# SENSORS.net
KiCad netlist of a schematic drawn in Altium Designer
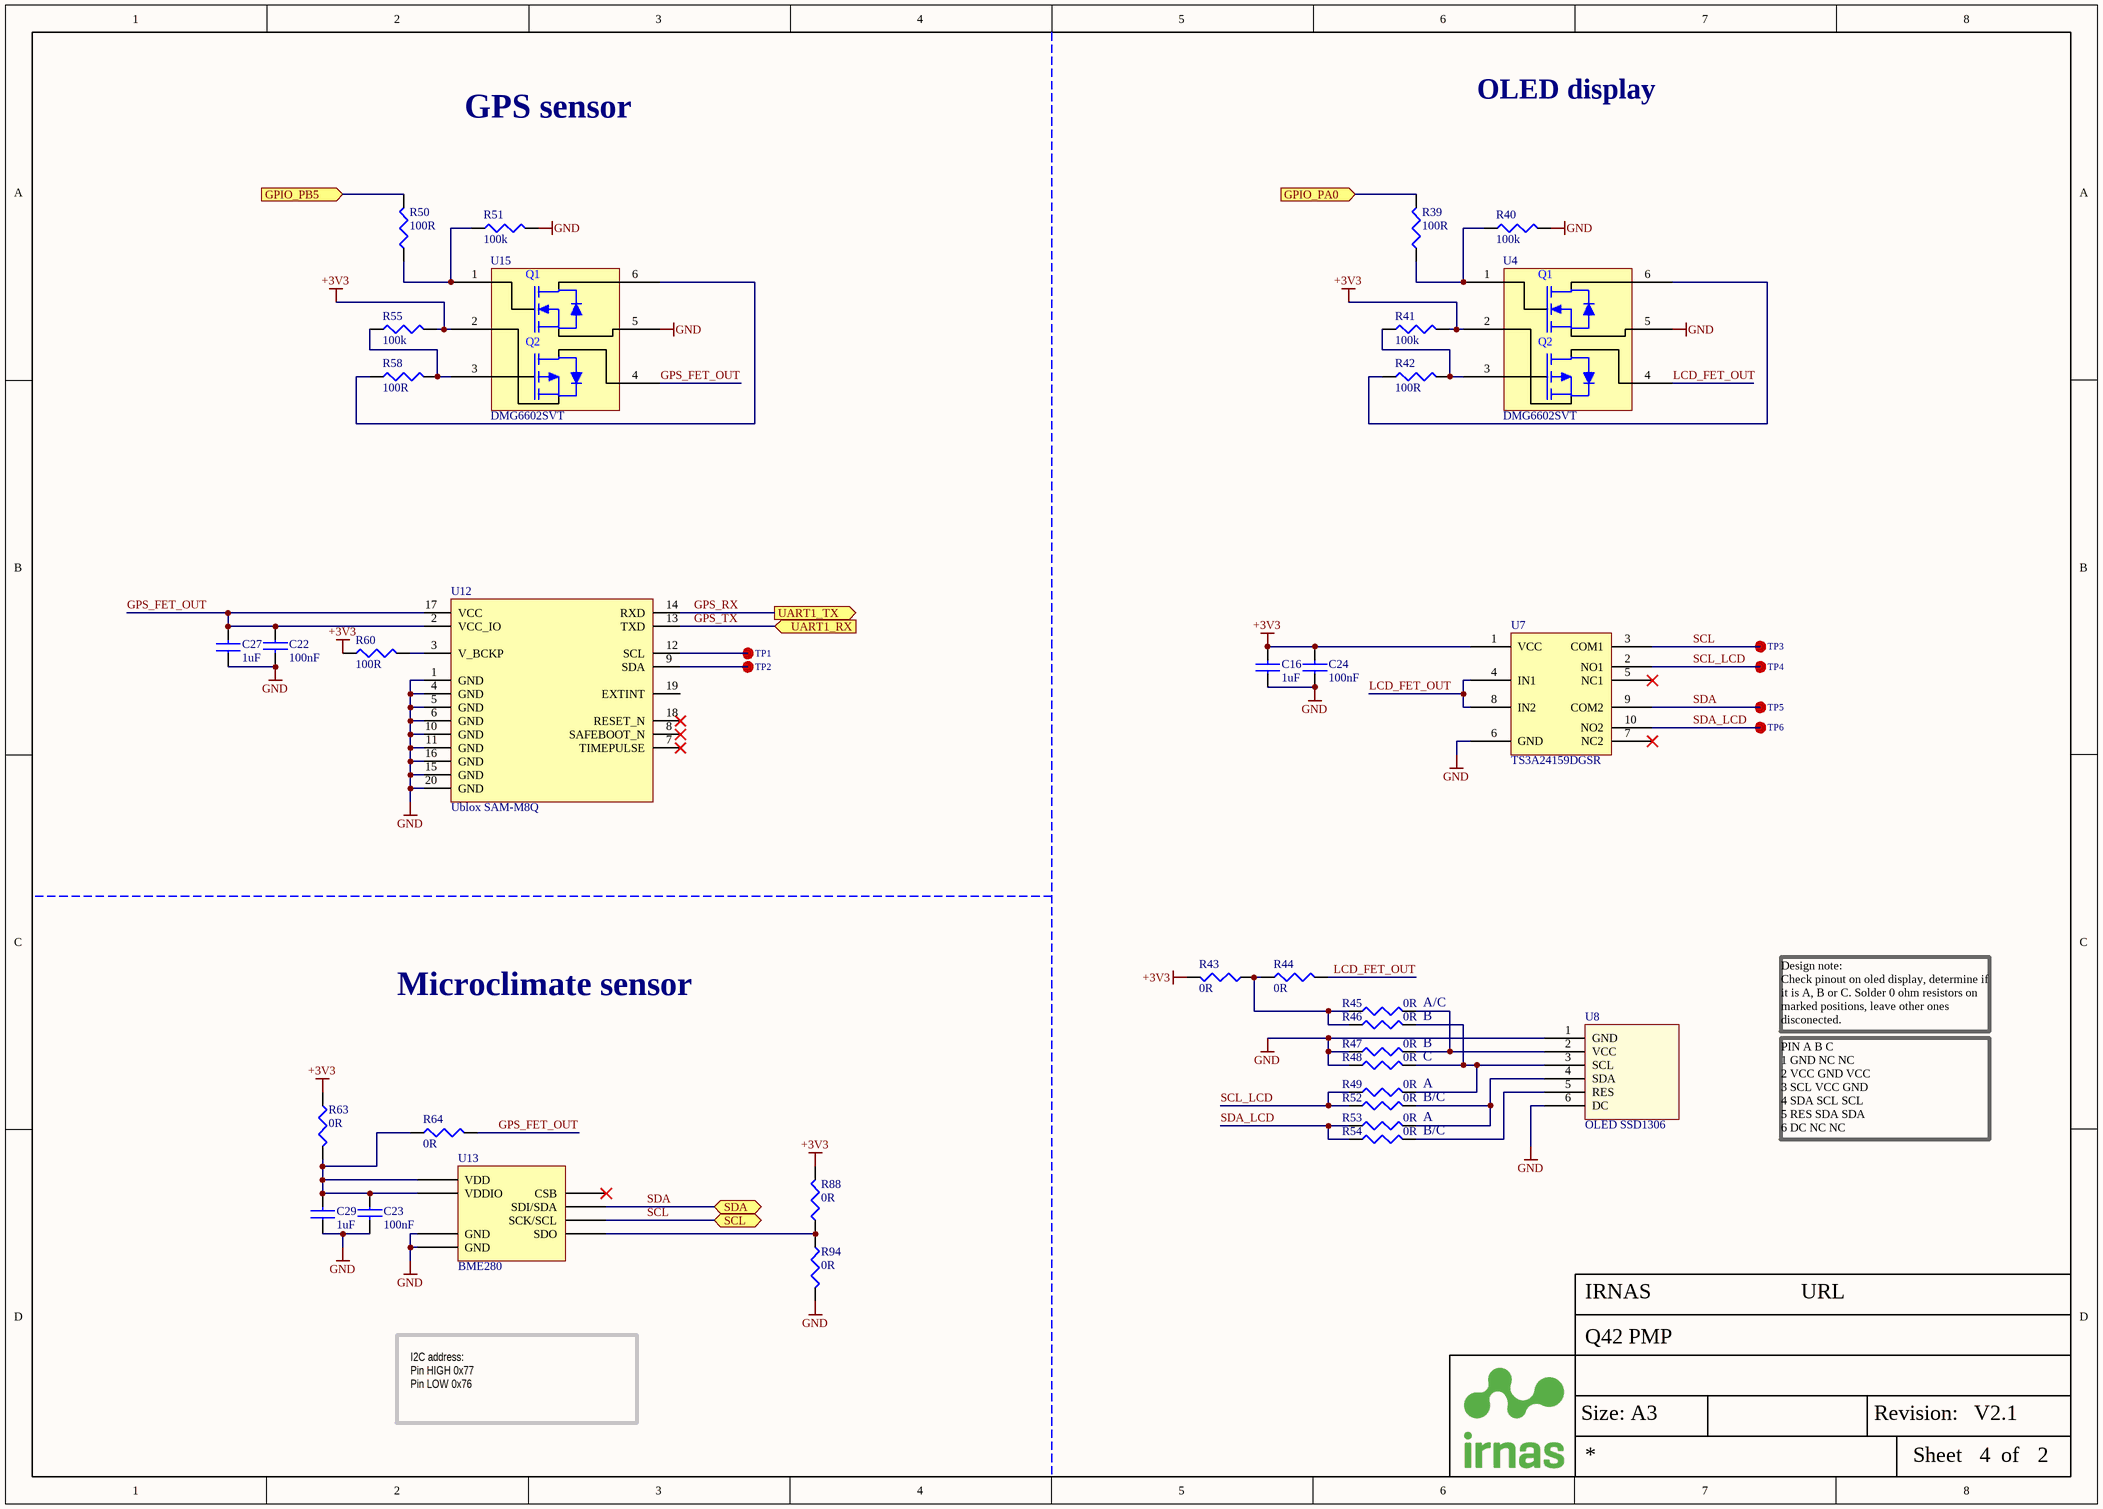
[diagram p0: SENSORS.SchDoc]

(export (version "E")
  (design (tool "Eeschema 10.0.6"))
  (components
    (comp (ref "C16")
      (value "1uF")
      (footprint "CAP0603")
      (description "MURATA - GRM188R61H105KAALD - CAP, MLCC, X5R, 1UF, 50V, 0603")
      (fields
        (field (name "MANUFACTURER") "MURATA")
        (field (name "MANUFACTURER PART NUMBER") "GRM188R61H105KAALD")
      )
      (libsource (lib "Passive") (part "C - 1uF"))
    )
    (comp (ref "C22")
      (value "100nF")
      (footprint "CAP0603")
      (description "MURATA - GRM188R71C104KA01J - CAP, MLCC, X7R, 0.1UF, 16V, 0603")
      (fields
        (field (name "MANUFACTURER") "MURATA")
        (field (name "MANUFACTURER PART NUMBER") "GRM188R71C104KA01J")
      )
      (libsource (lib "Passive") (part "C - 100nF"))
    )
    (comp (ref "C23")
      (value "100nF")
      (footprint "CAP0603")
      (description "MURATA - GRM188R71C104KA01J - CAP, MLCC, X7R, 0.1UF, 16V, 0603")
      (fields
        (field (name "MANUFACTURER") "MURATA")
        (field (name "MANUFACTURER PART NUMBER") "GRM188R71C104KA01J")
      )
      (libsource (lib "Passive") (part "C - 100nF"))
    )
    (comp (ref "C24")
      (value "100nF")
      (footprint "CAP0603")
      (description "MURATA - GRM188R71C104KA01J - CAP, MLCC, X7R, 0.1UF, 16V, 0603")
      (fields
        (field (name "MANUFACTURER") "MURATA")
        (field (name "MANUFACTURER PART NUMBER") "GRM188R71C104KA01J")
      )
      (libsource (lib "Passive") (part "C - 100nF"))
    )
    (comp (ref "C27")
      (value "1uF")
      (footprint "CAP0603")
      (description "MURATA - GRM188R61H105KAALD - CAP, MLCC, X5R, 1UF, 50V, 0603")
      (fields
        (field (name "MANUFACTURER") "MURATA")
        (field (name "MANUFACTURER PART NUMBER") "GRM188R61H105KAALD")
      )
      (libsource (lib "Passive") (part "C - 1uF"))
    )
    (comp (ref "C29")
      (value "1uF")
      (footprint "CAP0603")
      (description "MURATA - GRM188R61H105KAALD - CAP, MLCC, X5R, 1UF, 50V, 0603")
      (fields
        (field (name "MANUFACTURER") "MURATA")
        (field (name "MANUFACTURER PART NUMBER") "GRM188R61H105KAALD")
      )
      (libsource (lib "Passive") (part "C - 1uF"))
    )
    (comp (ref "R39")
      (value "100R")
      (footprint "RES0603")
      (description "MULTICOMP - MC0063W06031100R - RES, THICK FILM, 100R, 1%, 0.063W, 0603")
      (fields
        (field (name "MANUFACTURER") "MULTICOMP")
        (field (name "MANUFACTURER PART NUMBER") "MC0063W06031100R")
      )
      (libsource (lib "Passive") (part "R - 100R"))
    )
    (comp (ref "R40")
      (value "100k")
      (footprint "RES0603")
      (description "MULTICOMP - MCMR06X104 JTL - RES, CERAMIC, 100K, 5%, 0.1W, 0603")
      (fields
        (field (name "MANUFACTURER") "MULTICOMP")
        (field (name "MANUFACTURER PART NUMBER") "MCMR06X104 JTL")
      )
      (libsource (lib "Passive") (part "R - 100k"))
    )
    (comp (ref "R41")
      (value "100k")
      (footprint "RES0603")
      (description "MULTICOMP - MCMR06X104 JTL - RES, CERAMIC, 100K, 5%, 0.1W, 0603")
      (fields
        (field (name "MANUFACTURER") "MULTICOMP")
        (field (name "MANUFACTURER PART NUMBER") "MCMR06X104 JTL")
      )
      (libsource (lib "Passive") (part "R - 100k"))
    )
    (comp (ref "R42")
      (value "100R")
      (footprint "RES0603")
      (description "MULTICOMP - MC0063W06031100R - RES, THICK FILM, 100R, 1%, 0.063W, 0603")
      (fields
        (field (name "MANUFACTURER") "MULTICOMP")
        (field (name "MANUFACTURER PART NUMBER") "MC0063W06031100R")
      )
      (libsource (lib "Passive") (part "R - 100R"))
    )
    (comp (ref "R43")
      (value "0R")
      (footprint "RES0603")
      (description "BOURNS - CR0603-J/-000ELF - RES, THICK FILM, 0R, 5%, 0.1W, 0603")
      (fields
        (field (name "MANUFACTURER") "BOURNS")
        (field (name "MANUFACTURER PART NUMBER") "CR0603-J/-000ELF")
      )
      (libsource (lib "Passive") (part "R - 0R"))
    )
    (comp (ref "R44")
      (value "0R")
      (footprint "RES0603")
      (description "BOURNS - CR0603-J/-000ELF - RES, THICK FILM, 0R, 5%, 0.1W, 0603")
      (fields
        (field (name "MANUFACTURER") "BOURNS")
        (field (name "MANUFACTURER PART NUMBER") "CR0603-J/-000ELF")
      )
      (libsource (lib "Passive") (part "R - 0R"))
    )
    (comp (ref "R45")
      (value "0R")
      (footprint "RES0603")
      (description "BOURNS - CR0603-J/-000ELF - RES, THICK FILM, 0R, 5%, 0.1W, 0603")
      (fields
        (field (name "MANUFACTURER") "BOURNS")
        (field (name "MANUFACTURER PART NUMBER") "CR0603-J/-000ELF")
      )
      (libsource (lib "Passive") (part "R - 0R"))
    )
    (comp (ref "R46")
      (value "0R")
      (footprint "RES0603")
      (description "BOURNS - CR0603-J/-000ELF - RES, THICK FILM, 0R, 5%, 0.1W, 0603")
      (fields
        (field (name "MANUFACTURER") "BOURNS")
        (field (name "MANUFACTURER PART NUMBER") "CR0603-J/-000ELF")
      )
      (libsource (lib "Passive") (part "R - 0R"))
    )
    (comp (ref "R47")
      (value "0R")
      (footprint "RES0603")
      (description "BOURNS - CR0603-J/-000ELF - RES, THICK FILM, 0R, 5%, 0.1W, 0603")
      (fields
        (field (name "MANUFACTURER") "BOURNS")
        (field (name "MANUFACTURER PART NUMBER") "CR0603-J/-000ELF")
      )
      (libsource (lib "Passive") (part "R - 0R"))
    )
    (comp (ref "R48")
      (value "0R")
      (footprint "RES0603")
      (description "BOURNS - CR0603-J/-000ELF - RES, THICK FILM, 0R, 5%, 0.1W, 0603")
      (fields
        (field (name "MANUFACTURER") "BOURNS")
        (field (name "MANUFACTURER PART NUMBER") "CR0603-J/-000ELF")
      )
      (libsource (lib "Passive") (part "R - 0R"))
    )
    (comp (ref "R49")
      (value "0R")
      (footprint "RES0603")
      (description "BOURNS - CR0603-J/-000ELF - RES, THICK FILM, 0R, 5%, 0.1W, 0603")
      (fields
        (field (name "MANUFACTURER") "BOURNS")
        (field (name "MANUFACTURER PART NUMBER") "CR0603-J/-000ELF")
      )
      (libsource (lib "Passive") (part "R - 0R"))
    )
    (comp (ref "R50")
      (value "100R")
      (footprint "RES0603")
      (description "MULTICOMP - MC0063W06031100R - RES, THICK FILM, 100R, 1%, 0.063W, 0603")
      (fields
        (field (name "MANUFACTURER") "MULTICOMP")
        (field (name "MANUFACTURER PART NUMBER") "MC0063W06031100R")
      )
      (libsource (lib "Passive") (part "R - 100R"))
    )
    (comp (ref "R51")
      (value "100k")
      (footprint "RES0603")
      (description "MULTICOMP - MCMR06X104 JTL - RES, CERAMIC, 100K, 5%, 0.1W, 0603")
      (fields
        (field (name "MANUFACTURER") "MULTICOMP")
        (field (name "MANUFACTURER PART NUMBER") "MCMR06X104 JTL")
      )
      (libsource (lib "Passive") (part "R - 100k"))
    )
    (comp (ref "R52")
      (value "0R")
      (footprint "RES0603")
      (description "BOURNS - CR0603-J/-000ELF - RES, THICK FILM, 0R, 5%, 0.1W, 0603")
      (fields
        (field (name "MANUFACTURER") "BOURNS")
        (field (name "MANUFACTURER PART NUMBER") "CR0603-J/-000ELF")
      )
      (libsource (lib "Passive") (part "R - 0R"))
    )
    (comp (ref "R53")
      (value "0R")
      (footprint "RES0603")
      (description "BOURNS - CR0603-J/-000ELF - RES, THICK FILM, 0R, 5%, 0.1W, 0603")
      (fields
        (field (name "MANUFACTURER") "BOURNS")
        (field (name "MANUFACTURER PART NUMBER") "CR0603-J/-000ELF")
      )
      (libsource (lib "Passive") (part "R - 0R"))
    )
    (comp (ref "R54")
      (value "0R")
      (footprint "RES0603")
      (description "BOURNS - CR0603-J/-000ELF - RES, THICK FILM, 0R, 5%, 0.1W, 0603")
      (fields
        (field (name "MANUFACTURER") "BOURNS")
        (field (name "MANUFACTURER PART NUMBER") "CR0603-J/-000ELF")
      )
      (libsource (lib "Passive") (part "R - 0R"))
    )
    (comp (ref "R55")
      (value "100k")
      (footprint "RES0603")
      (description "MULTICOMP - MCMR06X104 JTL - RES, CERAMIC, 100K, 5%, 0.1W, 0603")
      (fields
        (field (name "MANUFACTURER") "MULTICOMP")
        (field (name "MANUFACTURER PART NUMBER") "MCMR06X104 JTL")
      )
      (libsource (lib "Passive") (part "R - 100k"))
    )
    (comp (ref "R58")
      (value "100R")
      (footprint "RES0603")
      (description "MULTICOMP - MC0063W06031100R - RES, THICK FILM, 100R, 1%, 0.063W, 0603")
      (fields
        (field (name "MANUFACTURER") "MULTICOMP")
        (field (name "MANUFACTURER PART NUMBER") "MC0063W06031100R")
      )
      (libsource (lib "Passive") (part "R - 100R"))
    )
    (comp (ref "R60")
      (value "100R")
      (footprint "RES0603")
      (description "MULTICOMP - MC0063W06031100R - RES, THICK FILM, 100R, 1%, 0.063W, 0603")
      (fields
        (field (name "MANUFACTURER") "MULTICOMP")
        (field (name "MANUFACTURER PART NUMBER") "MC0063W06031100R")
      )
      (libsource (lib "Passive") (part "R - 100R"))
    )
    (comp (ref "R63")
      (value "0R")
      (footprint "RES0603")
      (description "BOURNS - CR0603-J/-000ELF - RES, THICK FILM, 0R, 5%, 0.1W, 0603")
      (fields
        (field (name "MANUFACTURER") "BOURNS")
        (field (name "MANUFACTURER PART NUMBER") "CR0603-J/-000ELF")
      )
      (libsource (lib "Passive") (part "R - 0R"))
    )
    (comp (ref "R64")
      (value "0R")
      (footprint "RES0603")
      (description "BOURNS - CR0603-J/-000ELF - RES, THICK FILM, 0R, 5%, 0.1W, 0603")
      (fields
        (field (name "MANUFACTURER") "BOURNS")
        (field (name "MANUFACTURER PART NUMBER") "CR0603-J/-000ELF")
      )
      (libsource (lib "Passive") (part "R - 0R"))
    )
    (comp (ref "R88")
      (value "0R")
      (footprint "RES0603")
      (description "BOURNS - CR0603-J/-000ELF - RES, THICK FILM, 0R, 5%, 0.1W, 0603")
      (fields
        (field (name "MANUFACTURER") "BOURNS")
        (field (name "MANUFACTURER PART NUMBER") "CR0603-J/-000ELF")
      )
      (libsource (lib "Passive") (part "R - 0R"))
    )
    (comp (ref "R94")
      (value "0R")
      (footprint "RES0603")
      (description "BOURNS - CR0603-J/-000ELF - RES, THICK FILM, 0R, 5%, 0.1W, 0603")
      (fields
        (field (name "MANUFACTURER") "BOURNS")
        (field (name "MANUFACTURER PART NUMBER") "CR0603-J/-000ELF")
      )
      (libsource (lib "Passive") (part "R - 0R"))
    )
    (comp (ref "TP1")
      (value "TestPoint")
      (footprint "Passive:TestPoint:1.2x1.2mm")
      (description "TEST POINT ROUND SMD")
      (libsource (lib "Passive") (part "TestPoint"))
    )
    (comp (ref "TP2")
      (value "TestPoint")
      (footprint "Passive:TestPoint:1.2x1.2mm")
      (description "TEST POINT ROUND SMD")
      (libsource (lib "Passive") (part "TestPoint"))
    )
    (comp (ref "TP3")
      (value "TestPoint")
      (footprint "Passive:TestPoint:1.2x1.2mm")
      (description "TEST POINT ROUND SMD")
      (libsource (lib "Passive") (part "TestPoint"))
    )
    (comp (ref "TP4")
      (value "TestPoint")
      (footprint "Passive:TestPoint:1.2x1.2mm")
      (description "TEST POINT ROUND SMD")
      (libsource (lib "Passive") (part "TestPoint"))
    )
    (comp (ref "TP5")
      (value "TestPoint")
      (footprint "Passive:TestPoint:1.2x1.2mm")
      (description "TEST POINT ROUND SMD")
      (libsource (lib "Passive") (part "TestPoint"))
    )
    (comp (ref "TP6")
      (value "TestPoint")
      (footprint "Passive:TestPoint:1.2x1.2mm")
      (description "TEST POINT ROUND SMD")
      (libsource (lib "Passive") (part "TestPoint"))
    )
    (comp (ref "U4")
      (value "DMG6602SVT")
      (footprint "TSOT26")
      (description "Dual MOSFET, N and P Channel, 3.4 A, 30 V, 0.038 ohm, 10 V, 1 V")
      (libsource (lib "Active") (part "T_M - DMG6602SVT"))
    )
    (comp (ref "U7")
      (value "TS3A24159DGSR")
      (footprint "VSSOP-10")
      (description "Analogue Switch, 2 Channels, SPDT, 0.34 ohm, 1.65V to 3.6V, VSSOP, 10 Pins")
      (libsource (lib "Active") (part "INT - TS3A24159DGSR"))
    )
    (comp (ref "U8")
      (value "OLED SSD1306")
      (footprint "OLED SSD1306")
      (libsource (lib "oled") (part "OLED SSD1306"))
    )
    (comp (ref "U12")
      (value "Ublox SAM-M8Q")
      (footprint "SAM-M8Q")
      (description "SAM-M8 RF Receiver BeiDou, Galileo, GLONASS, GNSS, GPS -160dBm")
      (fields (field (name "MANUFACTURER") "u-blox") (field (name "MANUFACTURER PART NUMBER") "MAX-M8Q-0"))
      (libsource (lib "Active") (part "RF - UBLOX-SAM-M8Q"))
    )
    (comp (ref "U13")
      (value "BME280")
      (footprint "BME280")
      (description "Humidity Temperature Sensor 0 ~ 100% RH I²C, SPI ±3% 1s Surface Mount")
      (libsource (lib "Active") (part "SEN - BME280"))
    )
    (comp (ref "U15")
      (value "DMG6602SVT")
      (footprint "TSOT26")
      (description "Dual MOSFET, N and P Channel, 3.4 A, 30 V, 0.038 ohm, 10 V, 1 V")
      (libsource (lib "Active") (part "T_M - DMG6602SVT"))
    )
  )
  (nets
    (net (code "1") (name "+3V3") (class "Default")
      (node (ref "C16") (pin "2") (pinfunction "2_2") (pintype "passive"))
      (node (ref "C24") (pin "2") (pinfunction "2_2") (pintype "passive"))
      (node (ref "R41") (pin "2") (pinfunction "2_2") (pintype "passive"))
      (node (ref "R43") (pin "2") (pinfunction "2_2") (pintype "passive"))
      (node (ref "R55") (pin "2") (pinfunction "2_2") (pintype "passive"))
      (node (ref "R60") (pin "1") (pinfunction "1_1") (pintype "passive"))
      (node (ref "R63") (pin "1") (pinfunction "1_1") (pintype "passive"))
      (node (ref "R88") (pin "2") (pinfunction "2_2") (pintype "passive"))
      (node (ref "U15") (pin "2") (pinfunction "S2_2") (pintype "open_collector"))
      (node (ref "U4") (pin "2") (pinfunction "S2_2") (pintype "open_collector"))
      (node (ref "U7") (pin "1") (pinfunction "VCC_1") (pintype "passive"))
    )
    (net (code "2") (name "/GPIO_PA0") (class "Default")
      (node (ref "R39") (pin "2") (pinfunction "2_2") (pintype "passive"))
    )
    (net (code "3") (name "/GPIO_PB5") (class "Default")
      (node (ref "R50") (pin "2") (pinfunction "2_2") (pintype "passive"))
    )
    (net (code "4") (name "/GPS_FET_OUT") (class "Default")
      (node (ref "C22") (pin "1") (pinfunction "1_1") (pintype "passive"))
      (node (ref "C27") (pin "2") (pinfunction "2_2") (pintype "passive"))
      (node (ref "R64") (pin "2") (pinfunction "2_2") (pintype "passive"))
      (node (ref "U12") (pin "17") (pinfunction "VCC_17") (pintype "passive"))
      (node (ref "U12") (pin "2") (pinfunction "VCC_IO_2") (pintype "passive"))
      (node (ref "U15") (pin "4") (pinfunction "D2_4") (pintype "open_collector"))
    )
    (net (code "5") (name "/GPS_RX") (class "Default")
      (node (ref "U12") (pin "14") (pinfunction "RXD_14") (pintype "passive"))
    )
    (net (code "6") (name "/GPS_TX") (class "Default")
      (node (ref "U12") (pin "13") (pinfunction "TXD_13") (pintype "passive"))
    )
    (net (code "7") (name "/LCD_FET_OUT") (class "Default")
      (node (ref "R44") (pin "2") (pinfunction "2_2") (pintype "passive"))
      (node (ref "U4") (pin "4") (pinfunction "D2_4") (pintype "open_collector"))
      (node (ref "U7") (pin "4") (pinfunction "IN1_4") (pintype "passive"))
      (node (ref "U7") (pin "8") (pinfunction "IN2_8") (pintype "passive"))
    )
    (net (code "8") (name "/SCL") (class "Default")
      (node (ref "TP3") (pin "0") (pinfunction "0_0") (pintype "passive"))
      (node (ref "U13") (pin "4") (pinfunction "SCK/SCL_4") (pintype "passive"))
      (node (ref "U7") (pin "3") (pinfunction "COM1_3") (pintype "passive"))
    )
    (net (code "9") (name "/SCL_LCD") (class "Default")
      (node (ref "R49") (pin "1") (pinfunction "1_1") (pintype "passive"))
      (node (ref "R52") (pin "1") (pinfunction "1_1") (pintype "passive"))
      (node (ref "TP4") (pin "0") (pinfunction "0_0") (pintype "passive"))
      (node (ref "U7") (pin "2") (pinfunction "NO1_2") (pintype "passive"))
    )
    (net (code "10") (name "/SDA") (class "Default")
      (node (ref "TP5") (pin "0") (pinfunction "0_0") (pintype "passive"))
      (node (ref "U13") (pin "3") (pinfunction "SDI/SDA_3") (pintype "passive"))
      (node (ref "U7") (pin "9") (pinfunction "COM2_9") (pintype "passive"))
    )
    (net (code "11") (name "/SDA_LCD") (class "Default")
      (node (ref "R53") (pin "1") (pinfunction "1_1") (pintype "passive"))
      (node (ref "R54") (pin "1") (pinfunction "1_1") (pintype "passive"))
      (node (ref "TP6") (pin "0") (pinfunction "0_0") (pintype "passive"))
      (node (ref "U7") (pin "10") (pinfunction "NO2_10") (pintype "passive"))
    )
    (net (code "12") (name "GND") (class "Default")
      (node (ref "C16") (pin "1") (pinfunction "1_1") (pintype "passive"))
      (node (ref "C22") (pin "2") (pinfunction "2_2") (pintype "passive"))
      (node (ref "C23") (pin "2") (pinfunction "2_2") (pintype "passive"))
      (node (ref "C24") (pin "1") (pinfunction "1_1") (pintype "passive"))
      (node (ref "C27") (pin "1") (pinfunction "1_1") (pintype "passive"))
      (node (ref "C29") (pin "1") (pinfunction "1_1") (pintype "passive"))
      (node (ref "R40") (pin "2") (pinfunction "2_2") (pintype "passive"))
      (node (ref "R47") (pin "1") (pinfunction "1_1") (pintype "passive"))
      (node (ref "R48") (pin "1") (pinfunction "1_1") (pintype "passive"))
      (node (ref "R51") (pin "2") (pinfunction "2_2") (pintype "passive"))
      (node (ref "R94") (pin "2") (pinfunction "2_2") (pintype "passive"))
      (node (ref "U12") (pin "1") (pinfunction "GND_1") (pintype "passive"))
      (node (ref "U12") (pin "10") (pinfunction "GND_10") (pintype "passive"))
      (node (ref "U12") (pin "11") (pinfunction "GND_11") (pintype "passive"))
      (node (ref "U12") (pin "15") (pinfunction "GND_15") (pintype "passive"))
      (node (ref "U12") (pin "16") (pinfunction "GND_16") (pintype "passive"))
      (node (ref "U12") (pin "20") (pinfunction "GND_20") (pintype "passive"))
      (node (ref "U12") (pin "4") (pinfunction "GND_4") (pintype "passive"))
      (node (ref "U12") (pin "5") (pinfunction "GND_5") (pintype "passive"))
      (node (ref "U12") (pin "6") (pinfunction "GND_6") (pintype "passive"))
      (node (ref "U13") (pin "1") (pinfunction "GND_1") (pintype "passive"))
      (node (ref "U13") (pin "7") (pinfunction "GND_7") (pintype "passive"))
      (node (ref "U15") (pin "5") (pinfunction "S1_5") (pintype "passive"))
      (node (ref "U4") (pin "5") (pinfunction "S1_5") (pintype "passive"))
      (node (ref "U7") (pin "6") (pinfunction "GND_6") (pintype "passive"))
      (node (ref "U8") (pin "1") (pinfunction "GND_1") (pintype "passive"))
      (node (ref "U8") (pin "6") (pinfunction "DC_6") (pintype "passive"))
    )
    (net (code "13") (name "Net-(R43-Pad1)") (class "Default")
      (node (ref "R43") (pin "1") (pinfunction "1_1") (pintype "passive"))
      (node (ref "R44") (pin "1") (pinfunction "1_1") (pintype "passive"))
      (node (ref "R45") (pin "1") (pinfunction "1_1") (pintype "passive"))
      (node (ref "R46") (pin "1") (pinfunction "1_1") (pintype "passive"))
    )
    (net (code "14") (name "Net-(U4-D1)") (class "Default")
      (node (ref "R42") (pin "1") (pinfunction "1_1") (pintype "passive"))
      (node (ref "U4") (pin "6") (pinfunction "D1_6") (pintype "open_collector"))
    )
    (net (code "15") (name "Net-(U4-G1)") (class "Default")
      (node (ref "R39") (pin "1") (pinfunction "1_1") (pintype "passive"))
      (node (ref "R40") (pin "1") (pinfunction "1_1") (pintype "passive"))
      (node (ref "U4") (pin "1") (pinfunction "G1_1") (pintype "open_collector"))
    )
    (net (code "16") (name "Net-(U4-G2)") (class "Default")
      (node (ref "R41") (pin "1") (pinfunction "1_1") (pintype "passive"))
      (node (ref "R42") (pin "2") (pinfunction "2_2") (pintype "passive"))
      (node (ref "U4") (pin "3") (pinfunction "G2_3") (pintype "open_collector"))
    )
    (net (code "17") (name "Net-(U8-RES)") (class "Default")
      (node (ref "R54") (pin "2") (pinfunction "2_2") (pintype "passive"))
      (node (ref "U8") (pin "5") (pinfunction "RES_5") (pintype "passive"))
    )
    (net (code "18") (name "Net-(U8-SCL)") (class "Default")
      (node (ref "R46") (pin "2") (pinfunction "2_2") (pintype "passive"))
      (node (ref "R48") (pin "2") (pinfunction "2_2") (pintype "passive"))
      (node (ref "R49") (pin "2") (pinfunction "2_2") (pintype "passive"))
      (node (ref "U8") (pin "3") (pinfunction "SCL_3") (pintype "passive"))
    )
    (net (code "19") (name "Net-(U8-SDA)") (class "Default")
      (node (ref "R52") (pin "2") (pinfunction "2_2") (pintype "passive"))
      (node (ref "R53") (pin "2") (pinfunction "2_2") (pintype "passive"))
      (node (ref "U8") (pin "4") (pinfunction "SDA_4") (pintype "passive"))
    )
    (net (code "20") (name "Net-(U8-VCC)") (class "Default")
      (node (ref "R45") (pin "2") (pinfunction "2_2") (pintype "passive"))
      (node (ref "R47") (pin "2") (pinfunction "2_2") (pintype "passive"))
      (node (ref "U8") (pin "2") (pinfunction "VCC_2") (pintype "passive"))
    )
    (net (code "21") (name "Net-(U12-SCL)") (class "Default")
      (node (ref "TP1") (pin "0") (pinfunction "0_0") (pintype "passive"))
      (node (ref "U12") (pin "12") (pinfunction "SCL_12") (pintype "passive"))
    )
    (net (code "22") (name "Net-(U12-SDA)") (class "Default")
      (node (ref "TP2") (pin "0") (pinfunction "0_0") (pintype "passive"))
      (node (ref "U12") (pin "9") (pinfunction "SDA_9") (pintype "passive"))
    )
    (net (code "23") (name "Net-(U12-V_BCKP)") (class "Default")
      (node (ref "R60") (pin "2") (pinfunction "2_2") (pintype "passive"))
      (node (ref "U12") (pin "3") (pinfunction "V_BCKP_3") (pintype "passive"))
    )
    (net (code "24") (name "Net-(U13-SDO)") (class "Default")
      (node (ref "R88") (pin "1") (pinfunction "1_1") (pintype "passive"))
      (node (ref "R94") (pin "1") (pinfunction "1_1") (pintype "passive"))
      (node (ref "U13") (pin "5") (pinfunction "SDO_5") (pintype "passive"))
    )
    (net (code "25") (name "Net-(U13-VDD)") (class "Default")
      (node (ref "C23") (pin "1") (pinfunction "1_1") (pintype "passive"))
      (node (ref "C29") (pin "2") (pinfunction "2_2") (pintype "passive"))
      (node (ref "R63") (pin "2") (pinfunction "2_2") (pintype "passive"))
      (node (ref "R64") (pin "1") (pinfunction "1_1") (pintype "passive"))
      (node (ref "U13") (pin "6") (pinfunction "VDDIO_6") (pintype "passive"))
      (node (ref "U13") (pin "8") (pinfunction "VDD_8") (pintype "passive"))
    )
    (net (code "26") (name "Net-(U15-D1)") (class "Default")
      (node (ref "R58") (pin "1") (pinfunction "1_1") (pintype "passive"))
      (node (ref "U15") (pin "6") (pinfunction "D1_6") (pintype "open_collector"))
    )
    (net (code "27") (name "Net-(U15-G1)") (class "Default")
      (node (ref "R50") (pin "1") (pinfunction "1_1") (pintype "passive"))
      (node (ref "R51") (pin "1") (pinfunction "1_1") (pintype "passive"))
      (node (ref "U15") (pin "1") (pinfunction "G1_1") (pintype "open_collector"))
    )
    (net (code "28") (name "Net-(U15-G2)") (class "Default")
      (node (ref "R55") (pin "1") (pinfunction "1_1") (pintype "passive"))
      (node (ref "R58") (pin "2") (pinfunction "2_2") (pintype "passive"))
      (node (ref "U15") (pin "3") (pinfunction "G2_3") (pintype "open_collector"))
    )
    (net (code "29") (name "unconnected-(U7-NC1-Pad5)") (class "Default")
      (node (ref "U7") (pin "5") (pinfunction "NC1_5") (pintype "passive+no_connect"))
    )
    (net (code "30") (name "unconnected-(U7-NC2-Pad7)") (class "Default")
      (node (ref "U7") (pin "7") (pinfunction "NC2_7") (pintype "passive+no_connect"))
    )
    (net (code "31") (name "unconnected-(U12-EXTINT-Pad19)") (class "Default")
      (node (ref "U12") (pin "19") (pinfunction "EXTINT_19") (pintype "passive"))
    )
    (net (code "32") (name "unconnected-(U12-RESET_N-Pad18)") (class "Default")
      (node (ref "U12") (pin "18") (pinfunction "RESET_N_18") (pintype "passive+no_connect"))
    )
    (net (code "33") (name "unconnected-(U12-SAFEBOOT_N-Pad8)") (class "Default")
      (node (ref "U12") (pin "8") (pinfunction "SAFEBOOT_N_8") (pintype "passive+no_connect"))
    )
    (net (code "34") (name "unconnected-(U12-TIMEPULSE-Pad7)") (class "Default")
      (node (ref "U12") (pin "7") (pinfunction "TIMEPULSE_7") (pintype "passive+no_connect"))
    )
    (net (code "35") (name "unconnected-(U13-CSB-Pad2)") (class "Default")
      (node (ref "U13") (pin "2") (pinfunction "CSB_2") (pintype "passive+no_connect"))
    )
  )
)
